# CCE_Magic_Wand_01.net
KiCad netlist of a schematic drawn in Altium Designer
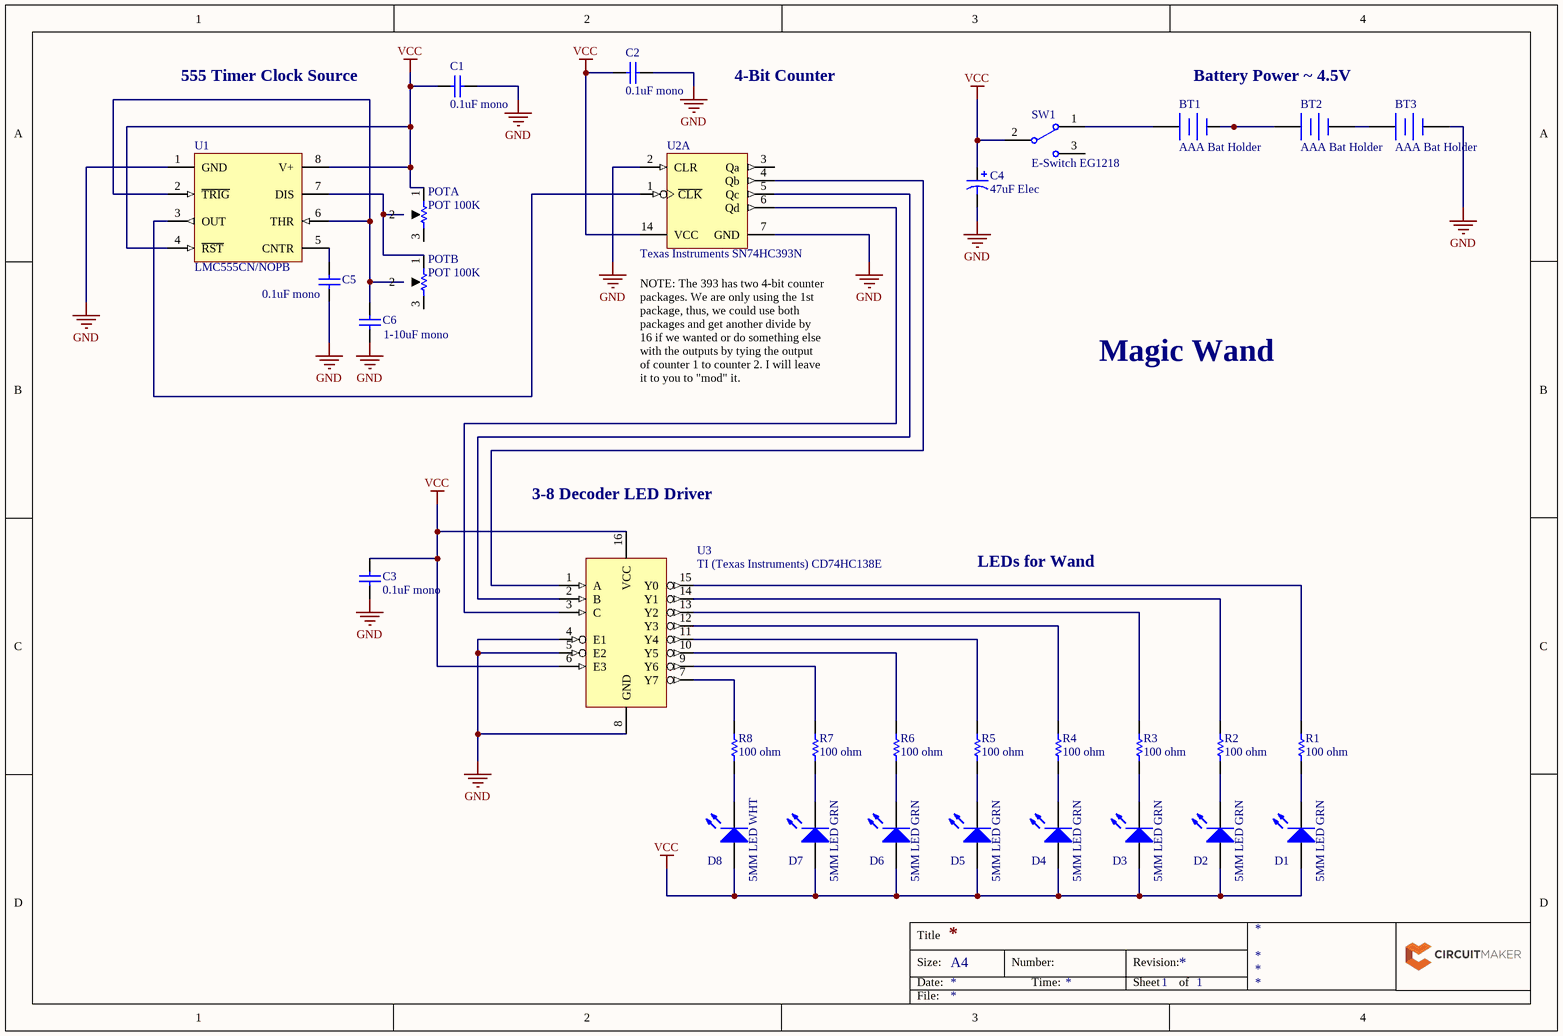
[diagram p0: CCE_Magic_Wand_01.SchDoc]

(export (version "E")
  (design (tool "Eeschema 10.0.6"))
  (components
    (comp (ref "BT1")
      (value "AAA Bat Holder")
      (footprint "PCB-3612-1")
      (description "HOLDER BATTERY 1CELL AAA PC MNT")
      (libsource (lib "CommunityVault") (part "CMP-3612-5"))
    )
    (comp (ref "BT2")
      (value "AAA Bat Holder")
      (footprint "PCB-3612-1")
      (description "HOLDER BATTERY 1CELL AAA PC MNT")
      (libsource (lib "CommunityVault") (part "CMP-3612-5"))
    )
    (comp (ref "BT3")
      (value "AAA Bat Holder")
      (footprint "PCB-3612-1")
      (description "HOLDER BATTERY 1CELL AAA PC MNT")
      (libsource (lib "CommunityVault") (part "CMP-3612-5"))
    )
    (comp (ref "C1")
      (value "0.1uF mono")
      (footprint "PCB-l4zci1ynknckpo24ombh-1")
      (description "Capacitor; Ceramic; Cap 0.1 uF; Tol -20, +80%; Vol-Rtg 50 VDC; Radial; Y5V; Tape & Reel")
      (fields (field (name "MANUFACTURER PART NUMBER") "K104Z15Y5VF5TL2"))
      (libsource (lib "Octopart library") (part "SYM-7d20b42952c2a2e7-1"))
    )
    (comp (ref "C2")
      (value "0.1uF mono")
      (footprint "PCB-l4zci1ynknckpo24ombh-1")
      (description "Capacitor; Ceramic; Cap 0.1 uF; Tol -20, +80%; Vol-Rtg 50 VDC; Radial; Y5V; Tape & Reel")
      (fields (field (name "MANUFACTURER PART NUMBER") "K104Z15Y5VF5TL2"))
      (libsource (lib "Octopart library") (part "SYM-7d20b42952c2a2e7-1"))
    )
    (comp (ref "C3")
      (value "0.1uF mono")
      (footprint "PCB-l4zci1ynknckpo24ombh-1")
      (description "Capacitor; Ceramic; Cap 0.1 uF; Tol -20, +80%; Vol-Rtg 50 VDC; Radial; Y5V; Tape & Reel")
      (fields (field (name "MANUFACTURER PART NUMBER") "K104Z15Y5VF5TL2"))
      (libsource (lib "Octopart library") (part "SYM-7d20b42952c2a2e7-1"))
    )
    (comp (ref "C4")
      (value "47uF Elec")
      (footprint "PCB-xswzn1jk2ejoevwvaoxh-1")
      (description "Electrolytic capacitor Radial lead 2.5 mm 10 µF 16 V 20 % (Ø) 4 mm Panasonic EEA-GA1C100H 1 pc(s)")
      (fields (field (name "MANUFACTURER PART NUMBER") "EEA-GA1C100H"))
      (libsource (lib "Octopart library") (part "SYM-b868704b0d3c67af-1"))
    )
    (comp (ref "C5")
      (value "0.1uF mono")
      (footprint "PCB-l4zci1ynknckpo24ombh-1")
      (description "Capacitor; Ceramic; Cap 0.1 uF; Tol -20, +80%; Vol-Rtg 50 VDC; Radial; Y5V; Tape & Reel")
      (fields (field (name "MANUFACTURER PART NUMBER") "K104Z15Y5VF5TL2"))
      (libsource (lib "Octopart library") (part "SYM-7d20b42952c2a2e7-1"))
    )
    (comp (ref "C6")
      (value "1-10uF mono")
      (footprint "PCB-l4zci1ynknckpo24ombh-1")
      (description "Capacitor; Ceramic; Cap 0.1 uF; Tol -20, +80%; Vol-Rtg 50 VDC; Radial; Y5V; Tape & Reel")
      (fields (field (name "MANUFACTURER PART NUMBER") "K104Z15Y5VF5TL2"))
      (libsource (lib "Octopart library") (part "SYM-7d20b42952c2a2e7-1"))
    )
    (comp (ref "D1")
      (value "5MM LED GRN")
      (footprint "PCB-b5vk7vz0xhkw7l0fnova-1")
      (description "LED Uni-Color Green 2-Pin T-1 3/4 Bulk")
      (fields
        (field (name "MANUFACTURER PART NUMBER") "C503B-GCN-CY0C0791")
        (field (name "MANUFACTURER") "Cree")
      )
      (libsource (lib "CommunityVault") (part "CMP-92bb5b2eff764d7c-3"))
    )
    (comp (ref "D2")
      (value "5MM LED GRN")
      (footprint "PCB-b5vk7vz0xhkw7l0fnova-1")
      (description "LED Uni-Color Green 2-Pin T-1 3/4 Bulk")
      (fields
        (field (name "MANUFACTURER PART NUMBER") "C503B-GCN-CY0C0791")
        (field (name "MANUFACTURER") "Cree")
      )
      (libsource (lib "CommunityVault") (part "CMP-92bb5b2eff764d7c-3"))
    )
    (comp (ref "D3")
      (value "5MM LED GRN")
      (footprint "PCB-b5vk7vz0xhkw7l0fnova-1")
      (description "LED Uni-Color Green 2-Pin T-1 3/4 Bulk")
      (fields
        (field (name "MANUFACTURER PART NUMBER") "C503B-GCN-CY0C0791")
        (field (name "MANUFACTURER") "Cree")
      )
      (libsource (lib "CommunityVault") (part "CMP-92bb5b2eff764d7c-3"))
    )
    (comp (ref "D4")
      (value "5MM LED GRN")
      (footprint "PCB-b5vk7vz0xhkw7l0fnova-1")
      (description "LED Uni-Color Green 2-Pin T-1 3/4 Bulk")
      (fields
        (field (name "MANUFACTURER PART NUMBER") "C503B-GCN-CY0C0791")
        (field (name "MANUFACTURER") "Cree")
      )
      (libsource (lib "CommunityVault") (part "CMP-92bb5b2eff764d7c-3"))
    )
    (comp (ref "D5")
      (value "5MM LED GRN")
      (footprint "PCB-b5vk7vz0xhkw7l0fnova-1")
      (description "LED Uni-Color Green 2-Pin T-1 3/4 Bulk")
      (fields
        (field (name "MANUFACTURER PART NUMBER") "C503B-GCN-CY0C0791")
        (field (name "MANUFACTURER") "Cree")
      )
      (libsource (lib "CommunityVault") (part "CMP-92bb5b2eff764d7c-3"))
    )
    (comp (ref "D6")
      (value "5MM LED GRN")
      (footprint "PCB-b5vk7vz0xhkw7l0fnova-1")
      (description "LED Uni-Color Green 2-Pin T-1 3/4 Bulk")
      (fields
        (field (name "MANUFACTURER PART NUMBER") "C503B-GCN-CY0C0791")
        (field (name "MANUFACTURER") "Cree")
      )
      (libsource (lib "CommunityVault") (part "CMP-92bb5b2eff764d7c-3"))
    )
    (comp (ref "D7")
      (value "5MM LED GRN")
      (footprint "PCB-b5vk7vz0xhkw7l0fnova-1")
      (description "LED Uni-Color Green 2-Pin T-1 3/4 Bulk")
      (fields
        (field (name "MANUFACTURER PART NUMBER") "C503B-GCN-CY0C0791")
        (field (name "MANUFACTURER") "Cree")
      )
      (libsource (lib "CommunityVault") (part "CMP-92bb5b2eff764d7c-3"))
    )
    (comp (ref "D8")
      (value "5MM LED WHT")
      (footprint "PCB-b5vk7vz0xhkw7l0fnova-1")
      (description "LED Uni-Color Green 2-Pin T-1 3/4 Bulk")
      (fields
        (field (name "MANUFACTURER PART NUMBER") "C503B-GCN-CY0C0791")
        (field (name "MANUFACTURER") "Cree")
      )
      (libsource (lib "CommunityVault") (part "CMP-92bb5b2eff764d7c-3"))
    )
    (comp (ref "POTA")
      (value "POT 100K")
      (footprint "PCB-j5qmepyewn2098kwld9k-1")
      (description "Res Cermet Trimmer 10K Ohm 10% 1/2W 1(Elec)/1(Mech)Turn 2.6mm (7 X 7 X 5.8mm) Pin Thru-Hole Bulk")
      (fields (field (name "MANUFACTURER PART NUMBER") "CT6EP103"))
      (libsource (lib "CommunityVault") (part "CMP-0fb4c6b6e673d073-3"))
    )
    (comp (ref "POTB")
      (value "POT 100K")
      (footprint "PCB-j5qmepyewn2098kwld9k-1")
      (description "Res Cermet Trimmer 10K Ohm 10% 1/2W 1(Elec)/1(Mech)Turn 2.6mm (7 X 7 X 5.8mm) Pin Thru-Hole Bulk")
      (fields (field (name "MANUFACTURER PART NUMBER") "CT6EP103"))
      (libsource (lib "CommunityVault") (part "CMP-0fb4c6b6e673d073-3"))
    )
    (comp (ref "R1")
      (value "100 ohm")
      (footprint "PCB-bfjjg625tt0lscyu35rt-1")
      (description "Res Carbon Film 1K Ohm 5% 1/4W -400ppm/°C to 0ppm/°C Conformal AXL Thru-Hole T/R")
      (fields (field (name "MANUFACTURER PART NUMBER") "CF14JT1K00"))
      (libsource (lib "CommunityVault") (part "CMP-db3e1311f37e04f9-1"))
    )
    (comp (ref "R2")
      (value "100 ohm")
      (footprint "PCB-bfjjg625tt0lscyu35rt-1")
      (description "Res Carbon Film 1K Ohm 5% 1/4W -400ppm/°C to 0ppm/°C Conformal AXL Thru-Hole T/R")
      (fields (field (name "MANUFACTURER PART NUMBER") "CF14JT1K00"))
      (libsource (lib "CommunityVault") (part "CMP-db3e1311f37e04f9-1"))
    )
    (comp (ref "R3")
      (value "100 ohm")
      (footprint "PCB-bfjjg625tt0lscyu35rt-1")
      (description "Res Carbon Film 1K Ohm 5% 1/4W -400ppm/°C to 0ppm/°C Conformal AXL Thru-Hole T/R")
      (fields (field (name "MANUFACTURER PART NUMBER") "CF14JT1K00"))
      (libsource (lib "CommunityVault") (part "CMP-db3e1311f37e04f9-1"))
    )
    (comp (ref "R4")
      (value "100 ohm")
      (footprint "PCB-bfjjg625tt0lscyu35rt-1")
      (description "Res Carbon Film 1K Ohm 5% 1/4W -400ppm/°C to 0ppm/°C Conformal AXL Thru-Hole T/R")
      (fields (field (name "MANUFACTURER PART NUMBER") "CF14JT1K00"))
      (libsource (lib "CommunityVault") (part "CMP-db3e1311f37e04f9-1"))
    )
    (comp (ref "R5")
      (value "100 ohm")
      (footprint "PCB-bfjjg625tt0lscyu35rt-1")
      (description "Res Carbon Film 1K Ohm 5% 1/4W -400ppm/°C to 0ppm/°C Conformal AXL Thru-Hole T/R")
      (fields (field (name "MANUFACTURER PART NUMBER") "CF14JT1K00"))
      (libsource (lib "CommunityVault") (part "CMP-db3e1311f37e04f9-1"))
    )
    (comp (ref "R6")
      (value "100 ohm")
      (footprint "PCB-bfjjg625tt0lscyu35rt-1")
      (description "Res Carbon Film 1K Ohm 5% 1/4W -400ppm/°C to 0ppm/°C Conformal AXL Thru-Hole T/R")
      (fields (field (name "MANUFACTURER PART NUMBER") "CF14JT1K00"))
      (libsource (lib "CommunityVault") (part "CMP-db3e1311f37e04f9-1"))
    )
    (comp (ref "R7")
      (value "100 ohm")
      (footprint "PCB-bfjjg625tt0lscyu35rt-1")
      (description "Res Carbon Film 1K Ohm 5% 1/4W -400ppm/°C to 0ppm/°C Conformal AXL Thru-Hole T/R")
      (fields (field (name "MANUFACTURER PART NUMBER") "CF14JT1K00"))
      (libsource (lib "CommunityVault") (part "CMP-db3e1311f37e04f9-1"))
    )
    (comp (ref "R8")
      (value "100 ohm")
      (footprint "PCB-bfjjg625tt0lscyu35rt-1")
      (description "Res Carbon Film 1K Ohm 5% 1/4W -400ppm/°C to 0ppm/°C Conformal AXL Thru-Hole T/R")
      (fields (field (name "MANUFACTURER PART NUMBER") "CF14JT1K00"))
      (libsource (lib "CommunityVault") (part "CMP-db3e1311f37e04f9-1"))
    )
    (comp (ref "SW1")
      (value "E-Switch EG1218")
      (footprint "ESWI-EG1218_V")
      (description "Slide Switch, 500 V, -20 to 70 degC, 3-Pin THD, RoHS")
      (fields (field (name "MANUFACTURER PART NUMBER") "EG1218"))
      (libsource (lib "Octopart library") (part "SW-SPDT-3_B"))
    )
    (comp (ref "U1")
      (value "LMC555CN/NOPB")
      (footprint "N08E")
      (description "CMOS Timer, 8-pin MDIP, Pb-Free")
      (libsource (lib "Octopart library") (part "AN-TIMER-LMC555-8"))
    )
    (comp (ref "U2")
      (value "Texas Instruments SN74HC393N")
      (footprint "PCB-84al2o76zfufqnpnnbbm-1")
      (description "Counter/Divider Dual 4-Bit Binary UP 14-Pin PDIP Tube")
      (fields (field (name "MANUFACTURER PART NUMBER") "SN74HC393N"))
      (libsource (lib "Octopart library") (part "SYM-3c53f5596157e394-1"))
    )
    (comp (ref "U3")
      (value "TI (Texas Instruments) CD74HC138E")
      (footprint "PCB-1166716-1")
      (description "TEXAS INSTRUMENTS   CD74HC138E   Logic Type:Decoder / Demultiplexer")
      (fields
        (field (name "MANUFACTURER PART NUMBER") "CD74HC138E")
        (field (name "MANUFACTURER") "Texas Instruments")
      )
      (libsource (lib "Octopart library") (part "SYM-1166716-1"))
    )
  )
  (nets
    (net (code "1") (name "GND") (class "Default")
      (node (ref "BT3") (pin "2") (pinfunction "-_2") (pintype "passive"))
      (node (ref "C1") (pin "2") (pinfunction "2_2") (pintype "passive"))
      (node (ref "C2") (pin "2") (pinfunction "2_2") (pintype "passive"))
      (node (ref "C3") (pin "2") (pinfunction "2_2") (pintype "passive"))
      (node (ref "C4") (pin "-") (pinfunction "-_-") (pintype "passive"))
      (node (ref "C5") (pin "1") (pinfunction "1_1") (pintype "passive"))
      (node (ref "C6") (pin "1") (pinfunction "1_1") (pintype "passive"))
      (node (ref "U1") (pin "1") (pinfunction "GND_1") (pintype "power_in"))
      (node (ref "U2") (pin "2") (pinfunction "CLR_2") (pintype "input"))
      (node (ref "U2") (pin "7") (pinfunction "GND_7") (pintype "power_in"))
      (node (ref "U3") (pin "4") (pinfunction "E1_4") (pintype "input"))
      (node (ref "U3") (pin "5") (pinfunction "E2_5") (pintype "input"))
      (node (ref "U3") (pin "8") (pinfunction "GND_8") (pintype "power_in"))
    )
    (net (code "2") (name "Net-(BT1-+)") (class "Default")
      (node (ref "BT1") (pin "1") (pinfunction "+_1") (pintype "passive"))
      (node (ref "SW1") (pin "1") (pinfunction "1_1") (pintype "passive"))
    )
    (net (code "3") (name "Net-(BT1--)") (class "Default")
      (node (ref "BT1") (pin "2") (pinfunction "-_2") (pintype "passive"))
      (node (ref "BT2") (pin "1") (pinfunction "+_1") (pintype "passive"))
    )
    (net (code "4") (name "Net-(BT2--)") (class "Default")
      (node (ref "BT2") (pin "2") (pinfunction "-_2") (pintype "passive"))
      (node (ref "BT3") (pin "1") (pinfunction "+_1") (pintype "passive"))
    )
    (net (code "5") (name "Net-(D1-K)") (class "Default")
      (node (ref "D1") (pin "1") (pinfunction "K_1") (pintype "passive"))
      (node (ref "R1") (pin "2") (pinfunction "2_2") (pintype "passive"))
    )
    (net (code "6") (name "Net-(D2-K)") (class "Default")
      (node (ref "D2") (pin "1") (pinfunction "K_1") (pintype "passive"))
      (node (ref "R2") (pin "2") (pinfunction "2_2") (pintype "passive"))
    )
    (net (code "7") (name "Net-(D3-K)") (class "Default")
      (node (ref "D3") (pin "1") (pinfunction "K_1") (pintype "passive"))
      (node (ref "R3") (pin "2") (pinfunction "2_2") (pintype "passive"))
    )
    (net (code "8") (name "Net-(D4-K)") (class "Default")
      (node (ref "D4") (pin "1") (pinfunction "K_1") (pintype "passive"))
      (node (ref "R4") (pin "2") (pinfunction "2_2") (pintype "passive"))
    )
    (net (code "9") (name "Net-(D5-K)") (class "Default")
      (node (ref "D5") (pin "1") (pinfunction "K_1") (pintype "passive"))
      (node (ref "R5") (pin "2") (pinfunction "2_2") (pintype "passive"))
    )
    (net (code "10") (name "Net-(D6-K)") (class "Default")
      (node (ref "D6") (pin "1") (pinfunction "K_1") (pintype "passive"))
      (node (ref "R6") (pin "2") (pinfunction "2_2") (pintype "passive"))
    )
    (net (code "11") (name "Net-(D7-K)") (class "Default")
      (node (ref "D7") (pin "1") (pinfunction "K_1") (pintype "passive"))
      (node (ref "R7") (pin "2") (pinfunction "2_2") (pintype "passive"))
    )
    (net (code "12") (name "Net-(D8-K)") (class "Default")
      (node (ref "D8") (pin "1") (pinfunction "K_1") (pintype "passive"))
      (node (ref "R8") (pin "2") (pinfunction "2_2") (pintype "passive"))
    )
    (net (code "13") (name "Net-(U1-CNTR)") (class "Default")
      (node (ref "C5") (pin "2") (pinfunction "2_2") (pintype "passive"))
      (node (ref "U1") (pin "5") (pinfunction "CNTR_5") (pintype "passive"))
    )
    (net (code "14") (name "Net-(U1-DIS)") (class "Default")
      (node (ref "POTA") (pin "2") (pinfunction "2_2") (pintype "passive"))
      (node (ref "POTB") (pin "1") (pinfunction "1_1") (pintype "passive"))
      (node (ref "U1") (pin "7") (pinfunction "DIS_7") (pintype "open_collector"))
    )
    (net (code "15") (name "Net-(U1-OUT)") (class "Default")
      (node (ref "U1") (pin "3") (pinfunction "OUT_3") (pintype "output"))
      (node (ref "U2") (pin "1") (pinfunction "~{CLK}_1") (pintype "input"))
    )
    (net (code "16") (name "Net-(U1-THR)") (class "Default")
      (node (ref "C6") (pin "2") (pinfunction "2_2") (pintype "passive"))
      (node (ref "POTB") (pin "2") (pinfunction "2_2") (pintype "passive"))
      (node (ref "U1") (pin "2") (pinfunction "~{TRIG}_2") (pintype "input"))
      (node (ref "U1") (pin "6") (pinfunction "THR_6") (pintype "input"))
    )
    (net (code "17") (name "Net-(U2A-Qb)") (class "Default")
      (node (ref "U2") (pin "4") (pinfunction "Qb_4") (pintype "output"))
      (node (ref "U3") (pin "1") (pinfunction "A_1") (pintype "input"))
    )
    (net (code "18") (name "Net-(U2A-Qc)") (class "Default")
      (node (ref "U2") (pin "5") (pinfunction "Qc_5") (pintype "output"))
      (node (ref "U3") (pin "2") (pinfunction "B_2") (pintype "input"))
    )
    (net (code "19") (name "Net-(U2A-Qd)") (class "Default")
      (node (ref "U2") (pin "6") (pinfunction "Qd_6") (pintype "output"))
      (node (ref "U3") (pin "3") (pinfunction "C_3") (pintype "input"))
    )
    (net (code "20") (name "Net-(U3-Y0)") (class "Default")
      (node (ref "R1") (pin "1") (pinfunction "1_1") (pintype "passive"))
      (node (ref "U3") (pin "15") (pinfunction "Y0_15") (pintype "output"))
    )
    (net (code "21") (name "Net-(U3-Y1)") (class "Default")
      (node (ref "R2") (pin "1") (pinfunction "1_1") (pintype "passive"))
      (node (ref "U3") (pin "14") (pinfunction "Y1_14") (pintype "output"))
    )
    (net (code "22") (name "Net-(U3-Y2)") (class "Default")
      (node (ref "R3") (pin "1") (pinfunction "1_1") (pintype "passive"))
      (node (ref "U3") (pin "13") (pinfunction "Y2_13") (pintype "output"))
    )
    (net (code "23") (name "Net-(U3-Y3)") (class "Default")
      (node (ref "R4") (pin "1") (pinfunction "1_1") (pintype "passive"))
      (node (ref "U3") (pin "12") (pinfunction "Y3_12") (pintype "output"))
    )
    (net (code "24") (name "Net-(U3-Y4)") (class "Default")
      (node (ref "R5") (pin "1") (pinfunction "1_1") (pintype "passive"))
      (node (ref "U3") (pin "11") (pinfunction "Y4_11") (pintype "output"))
    )
    (net (code "25") (name "Net-(U3-Y5)") (class "Default")
      (node (ref "R6") (pin "1") (pinfunction "1_1") (pintype "passive"))
      (node (ref "U3") (pin "10") (pinfunction "Y5_10") (pintype "output"))
    )
    (net (code "26") (name "Net-(U3-Y6)") (class "Default")
      (node (ref "R7") (pin "1") (pinfunction "1_1") (pintype "passive"))
      (node (ref "U3") (pin "9") (pinfunction "Y6_9") (pintype "output"))
    )
    (net (code "27") (name "Net-(U3-Y7)") (class "Default")
      (node (ref "R8") (pin "1") (pinfunction "1_1") (pintype "passive"))
      (node (ref "U3") (pin "7") (pinfunction "Y7_7") (pintype "output"))
    )
    (net (code "28") (name "VCC") (class "Default")
      (node (ref "C1") (pin "1") (pinfunction "1_1") (pintype "passive"))
      (node (ref "C2") (pin "1") (pinfunction "1_1") (pintype "passive"))
      (node (ref "C3") (pin "1") (pinfunction "1_1") (pintype "passive"))
      (node (ref "C4") (pin "+") (pinfunction "+_+") (pintype "passive"))
      (node (ref "D1") (pin "2") (pinfunction "A_2") (pintype "passive"))
      (node (ref "D2") (pin "2") (pinfunction "A_2") (pintype "passive"))
      (node (ref "D3") (pin "2") (pinfunction "A_2") (pintype "passive"))
      (node (ref "D4") (pin "2") (pinfunction "A_2") (pintype "passive"))
      (node (ref "D5") (pin "2") (pinfunction "A_2") (pintype "passive"))
      (node (ref "D6") (pin "2") (pinfunction "A_2") (pintype "passive"))
      (node (ref "D7") (pin "2") (pinfunction "A_2") (pintype "passive"))
      (node (ref "D8") (pin "2") (pinfunction "A_2") (pintype "passive"))
      (node (ref "POTA") (pin "1") (pinfunction "1_1") (pintype "passive"))
      (node (ref "SW1") (pin "2") (pinfunction "COM_2") (pintype "passive"))
      (node (ref "U1") (pin "4") (pinfunction "~{RST}_4") (pintype "input"))
      (node (ref "U1") (pin "8") (pinfunction "V+_8") (pintype "power_in"))
      (node (ref "U2") (pin "14") (pinfunction "VCC_14") (pintype "power_in"))
      (node (ref "U3") (pin "16") (pinfunction "VCC_16") (pintype "power_in"))
      (node (ref "U3") (pin "6") (pinfunction "E3_6") (pintype "input"))
    )
    (net (code "29") (name "unconnected-(POTA-Pad3)") (class "Default")
      (node (ref "POTA") (pin "3") (pinfunction "3_3") (pintype "passive"))
    )
    (net (code "30") (name "unconnected-(POTB-Pad3)") (class "Default")
      (node (ref "POTB") (pin "3") (pinfunction "3_3") (pintype "passive"))
    )
    (net (code "31") (name "unconnected-(SW1-Pad3)") (class "Default")
      (node (ref "SW1") (pin "3") (pinfunction "3_3") (pintype "passive"))
    )
    (net (code "32") (name "unconnected-(U2A-Qa-Pad3)") (class "Default")
      (node (ref "U2") (pin "3") (pinfunction "Qa_3") (pintype "output"))
    )
  )
)
